# TelemetryClick.net
KiCad netlist of a schematic drawn in Altium Designer
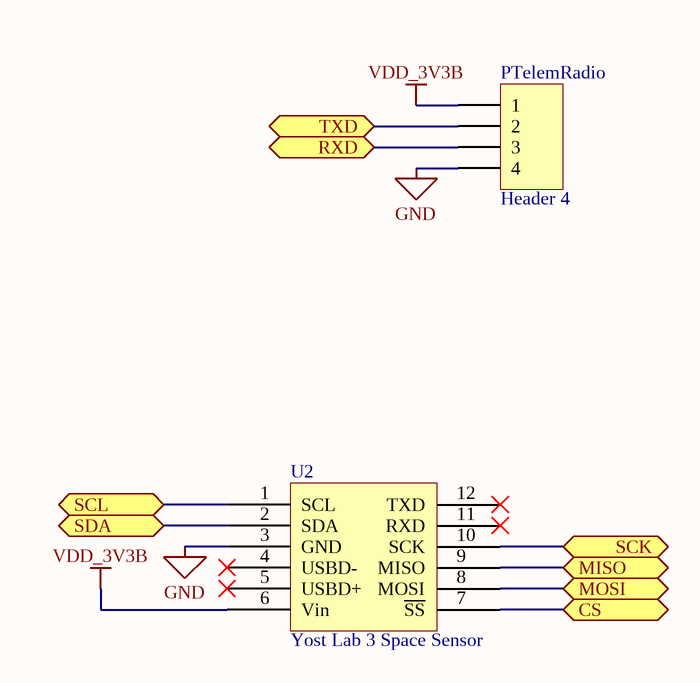
[diagram p0: TelemetryClick.SchDoc]

(export (version "E")
  (design (tool "Eeschema 10.0.6"))
  (components
    (comp (ref "PTelemRadio")
      (value "Header 4")
      (footprint "HDR1X4")
      (description "Header, 4-Pin")
      (fields (field (name "PUBLISHER") "Altium Limited"))
      (libsource (lib "Miscellaneous Connectors") (part "Header 4"))
    )
    (comp (ref "U2")
      (value "Yost Lab 3 Space Sensor")
      (footprint "Yost 3 Space Sensor")
      (libsource (lib "BeagleCape") (part "Yost Lab 3 Space Sensor"))
    )
  )
  (nets
    (net (code "1") (name "/CS") (class "Default")
      (node (ref "U2") (pin "7") (pinfunction "~{SS}_7") (pintype "passive"))
    )
    (net (code "2") (name "/MISO") (class "Default")
      (node (ref "U2") (pin "9") (pinfunction "MISO_9") (pintype "passive"))
    )
    (net (code "3") (name "/MOSI") (class "Default")
      (node (ref "U2") (pin "8") (pinfunction "MOSI_8") (pintype "passive"))
    )
    (net (code "4") (name "/RXD") (class "Default")
      (node (ref "PTelemRadio") (pin "3") (pinfunction "3_3") (pintype "passive"))
    )
    (net (code "5") (name "/SCK") (class "Default")
      (node (ref "U2") (pin "10") (pinfunction "SCK_10") (pintype "passive"))
    )
    (net (code "6") (name "/SCL") (class "Default")
      (node (ref "U2") (pin "1") (pinfunction "SCL_1") (pintype "passive"))
    )
    (net (code "7") (name "/SDA") (class "Default")
      (node (ref "U2") (pin "2") (pinfunction "SDA_2") (pintype "passive"))
    )
    (net (code "8") (name "/TXD") (class "Default")
      (node (ref "PTelemRadio") (pin "2") (pinfunction "2_2") (pintype "passive"))
    )
    (net (code "9") (name "GND") (class "Default")
      (node (ref "PTelemRadio") (pin "4") (pinfunction "4_4") (pintype "passive"))
      (node (ref "U2") (pin "3") (pinfunction "GND_3") (pintype "passive"))
    )
    (net (code "10") (name "VDD_3V3B") (class "Default")
      (node (ref "PTelemRadio") (pin "1") (pinfunction "1_1") (pintype "passive"))
      (node (ref "U2") (pin "6") (pinfunction "Vin_6") (pintype "passive"))
    )
    (net (code "11") (name "unconnected-(U2-RXD-Pad11)") (class "Default")
      (node (ref "U2") (pin "11") (pinfunction "RXD_11") (pintype "passive+no_connect"))
    )
    (net (code "12") (name "unconnected-(U2-TXD-Pad12)") (class "Default")
      (node (ref "U2") (pin "12") (pinfunction "TXD_12") (pintype "passive+no_connect"))
    )
    (net (code "13") (name "unconnected-(U2-USBD+-Pad5)") (class "Default")
      (node (ref "U2") (pin "5") (pinfunction "USBD+_5") (pintype "passive+no_connect"))
    )
    (net (code "14") (name "unconnected-(U2-USBD--Pad4)") (class "Default")
      (node (ref "U2") (pin "4") (pinfunction "USBD-_4") (pintype "passive+no_connect"))
    )
  )
)
